# coupeDeFrance.net
KiCad netlist of a schematic drawn in EAGLE
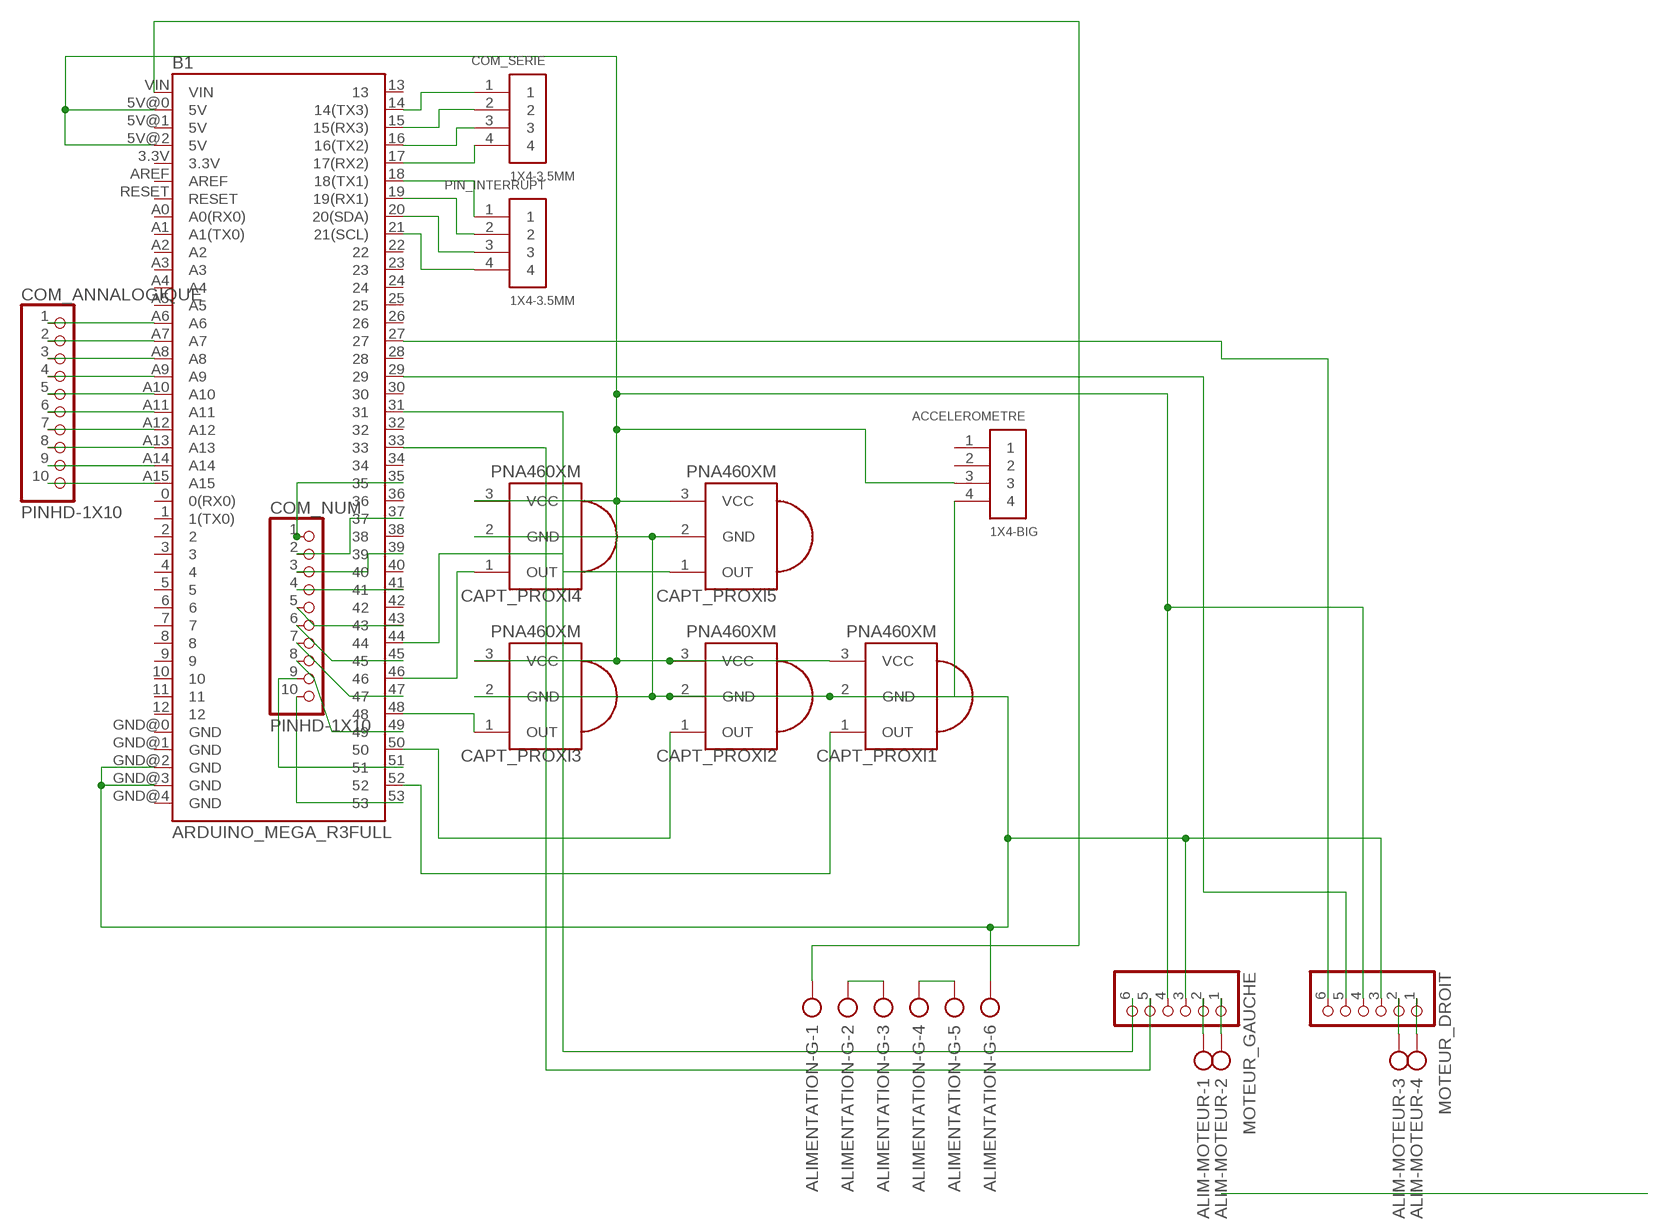
[diagram p0: schematic, sheet 1]

(export (version "E")
  (design (tool "Eeschema 10.0.6"))
  (components
    (comp (ref "ACCELEROMETRE")
      (value "1X4-BIG")
      (footprint "eagle-import:1X04-BIG")
      (libsource (lib "eagle-import") (part "1X4-BIG"))
    )
    (comp (ref "ALIM-MOTEUR")
      (value "AK300/4")
      (footprint "eagle-import:AK300_4")
      (libsource (lib "eagle-import") (part "AK300/4"))
    )
    (comp (ref "ALIMENTATION-G")
      (value "AK300/6")
      (footprint "eagle-import:AK300_6")
      (libsource (lib "eagle-import") (part "AK300/6"))
    )
    (comp (ref "B1")
      (value "ARDUINO_MEGA_R3FULL")
      (footprint "eagle-import:ARDUINO_MEGA")
      (libsource (lib "eagle-import") (part "ARDUINO_MEGA_R3FULL"))
    )
    (comp (ref "CAPT_PROXI1")
      (value "PNA460XM")
      (footprint "eagle-import:PNA460XM")
      (libsource (lib "eagle-import") (part "PNA460XM"))
    )
    (comp (ref "CAPT_PROXI2")
      (value "PNA460XM")
      (footprint "eagle-import:PNA460XM")
      (libsource (lib "eagle-import") (part "PNA460XM"))
    )
    (comp (ref "CAPT_PROXI3")
      (value "PNA460XM")
      (footprint "eagle-import:PNA460XM")
      (libsource (lib "eagle-import") (part "PNA460XM"))
    )
    (comp (ref "CAPT_PROXI4")
      (value "PNA460XM")
      (footprint "eagle-import:PNA460XM")
      (libsource (lib "eagle-import") (part "PNA460XM"))
    )
    (comp (ref "CAPT_PROXI5")
      (value "PNA460XM")
      (footprint "eagle-import:PNA460XM")
      (libsource (lib "eagle-import") (part "PNA460XM"))
    )
    (comp (ref "COM_ANNALOGIQUE")
      (value "PINHD-1X10")
      (footprint "eagle-import:1X10-BIG")
      (libsource (lib "eagle-import") (part "PINHD-1X10"))
    )
    (comp (ref "COM_NUM")
      (value "PINHD-1X10")
      (footprint "eagle-import:1X10-BIG")
      (libsource (lib "eagle-import") (part "PINHD-1X10"))
    )
    (comp (ref "COM_SERIE")
      (value "1X4-3.5MM")
      (footprint "eagle-import:1X04-3.5MM")
      (libsource (lib "eagle-import") (part "1X4-3.5MM"))
    )
    (comp (ref "MOTEUR_DROIT")
      (value "PINHD-1X6")
      (footprint "eagle-import:1X06")
      (libsource (lib "eagle-import") (part "PINHD-1X6"))
    )
    (comp (ref "MOTEUR_GAUCHE")
      (value "PINHD-1X6")
      (footprint "eagle-import:1X06")
      (libsource (lib "eagle-import") (part "PINHD-1X6"))
    )
    (comp (ref "PIN_INTERRUPT")
      (value "1X4-3.5MM")
      (footprint "eagle-import:1X04-3.5MM")
      (libsource (lib "eagle-import") (part "1X4-3.5MM"))
    )
  )
  (nets
    (net (code "1") (name "Net-(ALIM-MOTEURA-KL)") (class "Default")
      (node (ref "ALIM-MOTEUR") (pin "1") (pinfunction "KL_1") (pintype "passive"))
      (node (ref "MOTEUR_GAUCHE") (pin "2") (pinfunction "2_2") (pintype "passive"))
    )
    (net (code "2") (name "Net-(ALIM-MOTEURB-KL)") (class "Default")
      (node (ref "ALIM-MOTEUR") (pin "2") (pinfunction "KL_2") (pintype "passive"))
      (node (ref "MOTEUR_GAUCHE") (pin "1") (pinfunction "1_1") (pintype "passive"))
    )
    (net (code "3") (name "Net-(ALIM-MOTEURC-KL)") (class "Default")
      (node (ref "ALIM-MOTEUR") (pin "3") (pinfunction "KL_3") (pintype "passive"))
      (node (ref "MOTEUR_DROIT") (pin "2") (pinfunction "2_2") (pintype "passive"))
    )
    (net (code "4") (name "Net-(ALIM-MOTEURD-KL)") (class "Default")
      (node (ref "ALIM-MOTEUR") (pin "4") (pinfunction "KL_4") (pintype "passive"))
      (node (ref "MOTEUR_DROIT") (pin "1") (pinfunction "1_1") (pintype "passive"))
    )
    (net (code "5") (name "Net-(ALIMENTATION-GA-KL)") (class "Default")
      (node (ref "ALIMENTATION-G") (pin "1") (pinfunction "KL_1") (pintype "passive"))
      (node (ref "B1") (pin "VIN") (pinfunction "VIN_VIN") (pintype "bidirectional"))
    )
    (net (code "6") (name "Net-(ALIMENTATION-GB-KL)") (class "Default")
      (node (ref "ALIMENTATION-G") (pin "2") (pinfunction "KL_2") (pintype "passive"))
      (node (ref "ALIMENTATION-G") (pin "3") (pinfunction "KL_3") (pintype "passive"))
    )
    (net (code "7") (name "Net-(ALIMENTATION-GD-KL)") (class "Default")
      (node (ref "ALIMENTATION-G") (pin "4") (pinfunction "KL_4") (pintype "passive"))
      (node (ref "ALIMENTATION-G") (pin "5") (pinfunction "KL_5") (pintype "passive"))
    )
    (net (code "8") (name "Net-(ALIMENTATION-GF-KL)") (class "Default")
      (node (ref "ACCELEROMETRE") (pin "4") (pinfunction "4_4") (pintype "bidirectional"))
      (node (ref "ALIMENTATION-G") (pin "6") (pinfunction "KL_6") (pintype "passive"))
      (node (ref "B1") (pin "GND@2") (pinfunction "GND_GND@2") (pintype "bidirectional"))
      (node (ref "B1") (pin "GND@3") (pinfunction "GND_GND@3") (pintype "bidirectional"))
      (node (ref "CAPT_PROXI1") (pin "2") (pinfunction "GND_2") (pintype "power_in"))
      (node (ref "CAPT_PROXI2") (pin "2") (pinfunction "GND_2") (pintype "power_in"))
      (node (ref "CAPT_PROXI3") (pin "2") (pinfunction "GND_2") (pintype "power_in"))
      (node (ref "CAPT_PROXI4") (pin "2") (pinfunction "GND_2") (pintype "power_in"))
      (node (ref "CAPT_PROXI5") (pin "2") (pinfunction "GND_2") (pintype "power_in"))
      (node (ref "MOTEUR_DROIT") (pin "3") (pinfunction "3_3") (pintype "passive"))
      (node (ref "MOTEUR_GAUCHE") (pin "3") (pinfunction "3_3") (pintype "passive"))
    )
    (net (code "9") (name "Net-(B1-14(TX3))") (class "Default")
      (node (ref "B1") (pin "14") (pinfunction "14(TX3)_14") (pintype "bidirectional"))
      (node (ref "COM_SERIE") (pin "1") (pinfunction "1_1") (pintype "bidirectional"))
    )
    (net (code "10") (name "Net-(B1-15(RX3))") (class "Default")
      (node (ref "B1") (pin "15") (pinfunction "15(RX3)_15") (pintype "bidirectional"))
      (node (ref "COM_SERIE") (pin "2") (pinfunction "2_2") (pintype "bidirectional"))
    )
    (net (code "11") (name "Net-(B1-16(TX2))") (class "Default")
      (node (ref "B1") (pin "16") (pinfunction "16(TX2)_16") (pintype "bidirectional"))
      (node (ref "COM_SERIE") (pin "3") (pinfunction "3_3") (pintype "bidirectional"))
    )
    (net (code "12") (name "Net-(B1-17(RX2))") (class "Default")
      (node (ref "B1") (pin "17") (pinfunction "17(RX2)_17") (pintype "bidirectional"))
      (node (ref "COM_SERIE") (pin "4") (pinfunction "4_4") (pintype "bidirectional"))
    )
    (net (code "13") (name "Net-(B1-18(TX1))") (class "Default")
      (node (ref "B1") (pin "18") (pinfunction "18(TX1)_18") (pintype "bidirectional"))
      (node (ref "PIN_INTERRUPT") (pin "1") (pinfunction "1_1") (pintype "bidirectional"))
    )
    (net (code "14") (name "Net-(B1-19(RX1))") (class "Default")
      (node (ref "B1") (pin "19") (pinfunction "19(RX1)_19") (pintype "bidirectional"))
      (node (ref "PIN_INTERRUPT") (pin "2") (pinfunction "2_2") (pintype "bidirectional"))
    )
    (net (code "15") (name "Net-(B1-20(SDA))") (class "Default")
      (node (ref "B1") (pin "20") (pinfunction "20(SDA)_20") (pintype "bidirectional"))
      (node (ref "PIN_INTERRUPT") (pin "3") (pinfunction "3_3") (pintype "bidirectional"))
    )
    (net (code "16") (name "Net-(B1-21(SCL))") (class "Default")
      (node (ref "B1") (pin "21") (pinfunction "21(SCL)_21") (pintype "bidirectional"))
      (node (ref "PIN_INTERRUPT") (pin "4") (pinfunction "4_4") (pintype "bidirectional"))
    )
    (net (code "17") (name "Net-(B1-Pad27)") (class "Default")
      (node (ref "B1") (pin "27") (pinfunction "27_27") (pintype "bidirectional"))
      (node (ref "MOTEUR_DROIT") (pin "6") (pinfunction "6_6") (pintype "passive"))
    )
    (net (code "18") (name "Net-(B1-Pad29)") (class "Default")
      (node (ref "B1") (pin "29") (pinfunction "29_29") (pintype "bidirectional"))
      (node (ref "MOTEUR_DROIT") (pin "5") (pinfunction "5_5") (pintype "passive"))
    )
    (net (code "19") (name "Net-(B1-Pad31)") (class "Default")
      (node (ref "B1") (pin "31") (pinfunction "31_31") (pintype "bidirectional"))
      (node (ref "MOTEUR_GAUCHE") (pin "6") (pinfunction "6_6") (pintype "passive"))
    )
    (net (code "20") (name "Net-(B1-Pad33)") (class "Default")
      (node (ref "B1") (pin "33") (pinfunction "33_33") (pintype "bidirectional"))
      (node (ref "MOTEUR_GAUCHE") (pin "5") (pinfunction "5_5") (pintype "passive"))
    )
    (net (code "21") (name "Net-(B1-Pad35)") (class "Default")
      (node (ref "B1") (pin "35") (pinfunction "35_35") (pintype "bidirectional"))
      (node (ref "COM_NUM") (pin "1") (pinfunction "1_1") (pintype "passive"))
    )
    (net (code "22") (name "Net-(B1-Pad37)") (class "Default")
      (node (ref "B1") (pin "37") (pinfunction "37_37") (pintype "bidirectional"))
      (node (ref "COM_NUM") (pin "2") (pinfunction "2_2") (pintype "passive"))
    )
    (net (code "23") (name "Net-(B1-Pad39)") (class "Default")
      (node (ref "B1") (pin "39") (pinfunction "39_39") (pintype "bidirectional"))
      (node (ref "COM_NUM") (pin "3") (pinfunction "3_3") (pintype "passive"))
    )
    (net (code "24") (name "Net-(B1-Pad41)") (class "Default")
      (node (ref "B1") (pin "41") (pinfunction "41_41") (pintype "bidirectional"))
      (node (ref "COM_NUM") (pin "4") (pinfunction "4_4") (pintype "passive"))
    )
    (net (code "25") (name "Net-(B1-Pad43)") (class "Default")
      (node (ref "B1") (pin "43") (pinfunction "43_43") (pintype "bidirectional"))
      (node (ref "COM_NUM") (pin "5") (pinfunction "5_5") (pintype "passive"))
    )
    (net (code "26") (name "Net-(B1-Pad45)") (class "Default")
      (node (ref "B1") (pin "45") (pinfunction "45_45") (pintype "bidirectional"))
      (node (ref "COM_NUM") (pin "6") (pinfunction "6_6") (pintype "passive"))
    )
    (net (code "27") (name "Net-(B1-Pad47)") (class "Default")
      (node (ref "B1") (pin "47") (pinfunction "47_47") (pintype "bidirectional"))
      (node (ref "COM_NUM") (pin "7") (pinfunction "7_7") (pintype "passive"))
    )
    (net (code "28") (name "Net-(B1-Pad49)") (class "Default")
      (node (ref "B1") (pin "49") (pinfunction "49_49") (pintype "bidirectional"))
      (node (ref "COM_NUM") (pin "8") (pinfunction "8_8") (pintype "passive"))
    )
    (net (code "29") (name "Net-(B1-Pad51)") (class "Default")
      (node (ref "B1") (pin "51") (pinfunction "51_51") (pintype "bidirectional"))
      (node (ref "COM_NUM") (pin "9") (pinfunction "9_9") (pintype "passive"))
    )
    (net (code "30") (name "Net-(B1-Pad53)") (class "Default")
      (node (ref "B1") (pin "53") (pinfunction "53_53") (pintype "bidirectional"))
      (node (ref "COM_NUM") (pin "10") (pinfunction "10_10") (pintype "passive"))
    )
    (net (code "31") (name "Net-(B1-PadA6)") (class "Default")
      (node (ref "B1") (pin "A6") (pinfunction "A6_A6") (pintype "bidirectional"))
      (node (ref "COM_ANNALOGIQUE") (pin "1") (pinfunction "1_1") (pintype "passive"))
    )
    (net (code "32") (name "Net-(B1-PadA7)") (class "Default")
      (node (ref "B1") (pin "A7") (pinfunction "A7_A7") (pintype "bidirectional"))
      (node (ref "COM_ANNALOGIQUE") (pin "2") (pinfunction "2_2") (pintype "passive"))
    )
    (net (code "33") (name "Net-(B1-PadA8)") (class "Default")
      (node (ref "B1") (pin "A8") (pinfunction "A8_A8") (pintype "bidirectional"))
      (node (ref "COM_ANNALOGIQUE") (pin "3") (pinfunction "3_3") (pintype "passive"))
    )
    (net (code "34") (name "Net-(B1-PadA9)") (class "Default")
      (node (ref "B1") (pin "A9") (pinfunction "A9_A9") (pintype "bidirectional"))
      (node (ref "COM_ANNALOGIQUE") (pin "4") (pinfunction "4_4") (pintype "passive"))
    )
    (net (code "35") (name "Net-(B1-PadA10)") (class "Default")
      (node (ref "B1") (pin "A10") (pinfunction "A10_A10") (pintype "bidirectional"))
      (node (ref "COM_ANNALOGIQUE") (pin "5") (pinfunction "5_5") (pintype "passive"))
    )
    (net (code "36") (name "Net-(B1-PadA11)") (class "Default")
      (node (ref "B1") (pin "A11") (pinfunction "A11_A11") (pintype "bidirectional"))
      (node (ref "COM_ANNALOGIQUE") (pin "6") (pinfunction "6_6") (pintype "passive"))
    )
    (net (code "37") (name "Net-(B1-PadA12)") (class "Default")
      (node (ref "B1") (pin "A12") (pinfunction "A12_A12") (pintype "bidirectional"))
      (node (ref "COM_ANNALOGIQUE") (pin "7") (pinfunction "7_7") (pintype "passive"))
    )
    (net (code "38") (name "Net-(B1-PadA13)") (class "Default")
      (node (ref "B1") (pin "A13") (pinfunction "A13_A13") (pintype "bidirectional"))
      (node (ref "COM_ANNALOGIQUE") (pin "8") (pinfunction "8_8") (pintype "passive"))
    )
    (net (code "39") (name "Net-(B1-PadA14)") (class "Default")
      (node (ref "B1") (pin "A14") (pinfunction "A14_A14") (pintype "bidirectional"))
      (node (ref "COM_ANNALOGIQUE") (pin "9") (pinfunction "9_9") (pintype "passive"))
    )
    (net (code "40") (name "Net-(B1-PadA15)") (class "Default")
      (node (ref "B1") (pin "A15") (pinfunction "A15_A15") (pintype "bidirectional"))
      (node (ref "COM_ANNALOGIQUE") (pin "10") (pinfunction "10_10") (pintype "passive"))
    )
    (net (code "41") (name "Net-(CAPT_PROXI1-OUT)") (class "Default")
      (node (ref "B1") (pin "52") (pinfunction "52_52") (pintype "bidirectional"))
      (node (ref "CAPT_PROXI1") (pin "1") (pinfunction "OUT_1") (pintype "output"))
    )
    (net (code "42") (name "Net-(CAPT_PROXI1-VCC)") (class "Default")
      (node (ref "ACCELEROMETRE") (pin "3") (pinfunction "3_3") (pintype "bidirectional"))
      (node (ref "B1") (pin "5V@0") (pinfunction "5V_5V@0") (pintype "bidirectional"))
      (node (ref "B1") (pin "5V@2") (pinfunction "5V_5V@2") (pintype "bidirectional"))
      (node (ref "CAPT_PROXI1") (pin "3") (pinfunction "VCC_3") (pintype "power_in"))
      (node (ref "CAPT_PROXI2") (pin "3") (pinfunction "VCC_3") (pintype "power_in"))
      (node (ref "CAPT_PROXI3") (pin "3") (pinfunction "VCC_3") (pintype "power_in"))
      (node (ref "CAPT_PROXI4") (pin "3") (pinfunction "VCC_3") (pintype "power_in"))
      (node (ref "CAPT_PROXI5") (pin "3") (pinfunction "VCC_3") (pintype "power_in"))
      (node (ref "MOTEUR_DROIT") (pin "4") (pinfunction "4_4") (pintype "passive"))
      (node (ref "MOTEUR_GAUCHE") (pin "4") (pinfunction "4_4") (pintype "passive"))
    )
    (net (code "43") (name "Net-(CAPT_PROXI2-OUT)") (class "Default")
      (node (ref "B1") (pin "50") (pinfunction "50_50") (pintype "bidirectional"))
      (node (ref "CAPT_PROXI2") (pin "1") (pinfunction "OUT_1") (pintype "output"))
    )
    (net (code "44") (name "Net-(CAPT_PROXI3-OUT)") (class "Default")
      (node (ref "B1") (pin "48") (pinfunction "48_48") (pintype "bidirectional"))
      (node (ref "CAPT_PROXI3") (pin "1") (pinfunction "OUT_1") (pintype "output"))
    )
    (net (code "45") (name "Net-(CAPT_PROXI4-OUT)") (class "Default")
      (node (ref "B1") (pin "46") (pinfunction "46_46") (pintype "bidirectional"))
      (node (ref "CAPT_PROXI4") (pin "1") (pinfunction "OUT_1") (pintype "output"))
    )
    (net (code "46") (name "Net-(CAPT_PROXI5-OUT)") (class "Default")
      (node (ref "B1") (pin "44") (pinfunction "44_44") (pintype "bidirectional"))
      (node (ref "CAPT_PROXI5") (pin "1") (pinfunction "OUT_1") (pintype "output"))
    )
    (net (code "47") (name "unconnected-(ACCELEROMETRE-Pad1)") (class "Default")
      (node (ref "ACCELEROMETRE") (pin "1") (pinfunction "1_1") (pintype "bidirectional"))
    )
    (net (code "48") (name "unconnected-(ACCELEROMETRE-Pad2)") (class "Default")
      (node (ref "ACCELEROMETRE") (pin "2") (pinfunction "2_2") (pintype "bidirectional"))
    )
    (net (code "49") (name "unconnected-(B1-0(RX0)-Pad0)") (class "Default")
      (node (ref "B1") (pin "0") (pinfunction "0(RX0)_0") (pintype "bidirectional"))
    )
    (net (code "50") (name "unconnected-(B1-1(TX0)-Pad1)") (class "Default")
      (node (ref "B1") (pin "1") (pinfunction "1(TX0)_1") (pintype "bidirectional"))
    )
    (net (code "51") (name "unconnected-(B1-5V-Pad5V@1)") (class "Default")
      (node (ref "B1") (pin "5V@1") (pinfunction "5V_5V@1") (pintype "bidirectional"))
    )
    (net (code "52") (name "unconnected-(B1-A0(RX0)-PadA0)") (class "Default")
      (node (ref "B1") (pin "A0") (pinfunction "A0(RX0)_A0") (pintype "bidirectional"))
    )
    (net (code "53") (name "unconnected-(B1-A1(TX0)-PadA1)") (class "Default")
      (node (ref "B1") (pin "A1") (pinfunction "A1(TX0)_A1") (pintype "bidirectional"))
    )
    (net (code "54") (name "unconnected-(B1-GND-PadGND@0)") (class "Default")
      (node (ref "B1") (pin "GND@0") (pinfunction "GND_GND@0") (pintype "bidirectional"))
    )
    (net (code "55") (name "unconnected-(B1-GND-PadGND@1)") (class "Default")
      (node (ref "B1") (pin "GND@1") (pinfunction "GND_GND@1") (pintype "bidirectional"))
    )
    (net (code "56") (name "unconnected-(B1-GND-PadGND@4)") (class "Default")
      (node (ref "B1") (pin "GND@4") (pinfunction "GND_GND@4") (pintype "bidirectional"))
    )
    (net (code "57") (name "unconnected-(B1-Pad2)") (class "Default")
      (node (ref "B1") (pin "2") (pinfunction "2_2") (pintype "bidirectional"))
    )
    (net (code "58") (name "unconnected-(B1-Pad3)") (class "Default")
      (node (ref "B1") (pin "3") (pinfunction "3_3") (pintype "bidirectional"))
    )
    (net (code "59") (name "unconnected-(B1-Pad3.3V)") (class "Default")
      (node (ref "B1") (pin "3.3V") (pinfunction "3.3V_3.3V") (pintype "bidirectional"))
    )
    (net (code "60") (name "unconnected-(B1-Pad4)") (class "Default")
      (node (ref "B1") (pin "4") (pinfunction "4_4") (pintype "bidirectional"))
    )
    (net (code "61") (name "unconnected-(B1-Pad5)") (class "Default")
      (node (ref "B1") (pin "5") (pinfunction "5_5") (pintype "bidirectional"))
    )
    (net (code "62") (name "unconnected-(B1-Pad6)") (class "Default")
      (node (ref "B1") (pin "6") (pinfunction "6_6") (pintype "bidirectional"))
    )
    (net (code "63") (name "unconnected-(B1-Pad7)") (class "Default")
      (node (ref "B1") (pin "7") (pinfunction "7_7") (pintype "bidirectional"))
    )
    (net (code "64") (name "unconnected-(B1-Pad8)") (class "Default")
      (node (ref "B1") (pin "8") (pinfunction "8_8") (pintype "bidirectional"))
    )
    (net (code "65") (name "unconnected-(B1-Pad9)") (class "Default")
      (node (ref "B1") (pin "9") (pinfunction "9_9") (pintype "bidirectional"))
    )
    (net (code "66") (name "unconnected-(B1-Pad10)") (class "Default")
      (node (ref "B1") (pin "10") (pinfunction "10_10") (pintype "bidirectional"))
    )
    (net (code "67") (name "unconnected-(B1-Pad11)") (class "Default")
      (node (ref "B1") (pin "11") (pinfunction "11_11") (pintype "bidirectional"))
    )
    (net (code "68") (name "unconnected-(B1-Pad12)") (class "Default")
      (node (ref "B1") (pin "12") (pinfunction "12_12") (pintype "bidirectional"))
    )
    (net (code "69") (name "unconnected-(B1-Pad13)") (class "Default")
      (node (ref "B1") (pin "13") (pinfunction "13_13") (pintype "bidirectional"))
    )
    (net (code "70") (name "unconnected-(B1-Pad22)") (class "Default")
      (node (ref "B1") (pin "22") (pinfunction "22_22") (pintype "bidirectional"))
    )
    (net (code "71") (name "unconnected-(B1-Pad23)") (class "Default")
      (node (ref "B1") (pin "23") (pinfunction "23_23") (pintype "bidirectional"))
    )
    (net (code "72") (name "unconnected-(B1-Pad24)") (class "Default")
      (node (ref "B1") (pin "24") (pinfunction "24_24") (pintype "bidirectional"))
    )
    (net (code "73") (name "unconnected-(B1-Pad25)") (class "Default")
      (node (ref "B1") (pin "25") (pinfunction "25_25") (pintype "bidirectional"))
    )
    (net (code "74") (name "unconnected-(B1-Pad26)") (class "Default")
      (node (ref "B1") (pin "26") (pinfunction "26_26") (pintype "bidirectional"))
    )
    (net (code "75") (name "unconnected-(B1-Pad28)") (class "Default")
      (node (ref "B1") (pin "28") (pinfunction "28_28") (pintype "bidirectional"))
    )
    (net (code "76") (name "unconnected-(B1-Pad30)") (class "Default")
      (node (ref "B1") (pin "30") (pinfunction "30_30") (pintype "bidirectional"))
    )
    (net (code "77") (name "unconnected-(B1-Pad32)") (class "Default")
      (node (ref "B1") (pin "32") (pinfunction "32_32") (pintype "bidirectional"))
    )
    (net (code "78") (name "unconnected-(B1-Pad34)") (class "Default")
      (node (ref "B1") (pin "34") (pinfunction "34_34") (pintype "bidirectional"))
    )
    (net (code "79") (name "unconnected-(B1-Pad36)") (class "Default")
      (node (ref "B1") (pin "36") (pinfunction "36_36") (pintype "bidirectional"))
    )
    (net (code "80") (name "unconnected-(B1-Pad38)") (class "Default")
      (node (ref "B1") (pin "38") (pinfunction "38_38") (pintype "bidirectional"))
    )
    (net (code "81") (name "unconnected-(B1-Pad40)") (class "Default")
      (node (ref "B1") (pin "40") (pinfunction "40_40") (pintype "bidirectional"))
    )
    (net (code "82") (name "unconnected-(B1-Pad42)") (class "Default")
      (node (ref "B1") (pin "42") (pinfunction "42_42") (pintype "bidirectional"))
    )
    (net (code "83") (name "unconnected-(B1-PadA2)") (class "Default")
      (node (ref "B1") (pin "A2") (pinfunction "A2_A2") (pintype "bidirectional"))
    )
    (net (code "84") (name "unconnected-(B1-PadA3)") (class "Default")
      (node (ref "B1") (pin "A3") (pinfunction "A3_A3") (pintype "bidirectional"))
    )
    (net (code "85") (name "unconnected-(B1-PadA4)") (class "Default")
      (node (ref "B1") (pin "A4") (pinfunction "A4_A4") (pintype "bidirectional"))
    )
    (net (code "86") (name "unconnected-(B1-PadA5)") (class "Default")
      (node (ref "B1") (pin "A5") (pinfunction "A5_A5") (pintype "bidirectional"))
    )
    (net (code "87") (name "unconnected-(B1-PadAREF)") (class "Default")
      (node (ref "B1") (pin "AREF") (pinfunction "AREF_AREF") (pintype "bidirectional"))
    )
    (net (code "88") (name "unconnected-(B1-PadRESET)") (class "Default")
      (node (ref "B1") (pin "RESET") (pinfunction "RESET_RESET") (pintype "bidirectional"))
    )
  )
)
